# P10_Expander.net
KiCad netlist of a schematic drawn in Altium Designer
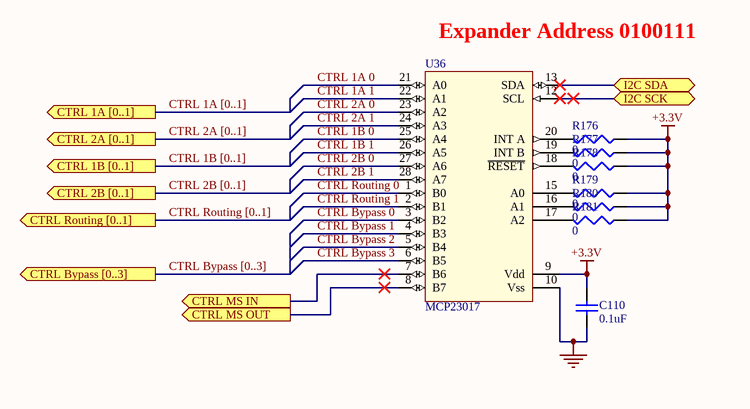
[diagram p0: P10_Expander.SchDoc]

(export (version "E")
  (design (tool "Eeschema 10.0.6"))
  (components
    (comp (ref "C110")
      (value "0.1uF")
      (footprint "CAP 0603 (1608 metric)")
      (description "Capacitor (Semiconductor SIM Model)")
      (libsource (lib "Miscellaneous Devices") (part "Cap Semi"))
    )
    (comp (ref "R176")
      (value "0")
      (footprint "RES 0603 (1608 metric)")
      (description "Resistor")
      (libsource (lib "Miscellaneous Devices") (part "Res3"))
    )
    (comp (ref "R177")
      (value "0")
      (footprint "RES 0603 (1608 metric)")
      (description "Resistor")
      (libsource (lib "Miscellaneous Devices") (part "Res3"))
    )
    (comp (ref "R178")
      (value "0")
      (footprint "RES 0603 (1608 metric)")
      (description "Resistor")
      (libsource (lib "Miscellaneous Devices") (part "Res3"))
    )
    (comp (ref "R179")
      (value "0")
      (footprint "RES 0603 (1608 metric)")
      (description "Resistor")
      (libsource (lib "Miscellaneous Devices") (part "Res3"))
    )
    (comp (ref "R180")
      (value "0")
      (footprint "RES 0603 (1608 metric)")
      (description "Resistor")
      (libsource (lib "Miscellaneous Devices") (part "Res3"))
    )
    (comp (ref "R181")
      (value "0")
      (footprint "RES 0603 (1608 metric)")
      (description "Resistor")
      (libsource (lib "Miscellaneous Devices") (part "Res3"))
    )
    (comp (ref "U36")
      (value "MCP23017")
      (description "16b I/O Expander")
      (libsource (lib "FilterPoC") (part "MCP23017"))
    )
  )
  (nets
    (net (code "1") (name "+3.3V") (class "Default")
      (node (ref "C110") (pin "1") (pinfunction "1_1") (pintype "passive"))
      (node (ref "R176") (pin "1") (pinfunction "1_1") (pintype "passive"))
      (node (ref "R177") (pin "1") (pinfunction "1_1") (pintype "passive"))
      (node (ref "R178") (pin "1") (pinfunction "1_1") (pintype "passive"))
      (node (ref "R179") (pin "1") (pinfunction "1_1") (pintype "passive"))
      (node (ref "R180") (pin "1") (pinfunction "1_1") (pintype "passive"))
      (node (ref "R181") (pin "1") (pinfunction "1_1") (pintype "passive"))
      (node (ref "U36") (pin "9") (pinfunction "Vdd_9") (pintype "power_in"))
    )
    (net (code "2") (name "/CTRL 1A 0") (class "Default")
      (node (ref "U36") (pin "21") (pinfunction "A0_21") (pintype "bidirectional"))
    )
    (net (code "3") (name "/CTRL 1A 1") (class "Default")
      (node (ref "U36") (pin "22") (pinfunction "A1_22") (pintype "bidirectional"))
    )
    (net (code "4") (name "/CTRL 1B 0") (class "Default")
      (node (ref "U36") (pin "25") (pinfunction "A4_25") (pintype "bidirectional"))
    )
    (net (code "5") (name "/CTRL 1B 1") (class "Default")
      (node (ref "U36") (pin "26") (pinfunction "A5_26") (pintype "bidirectional"))
    )
    (net (code "6") (name "/CTRL 2A 0") (class "Default")
      (node (ref "U36") (pin "23") (pinfunction "A2_23") (pintype "bidirectional"))
    )
    (net (code "7") (name "/CTRL 2A 1") (class "Default")
      (node (ref "U36") (pin "24") (pinfunction "A3_24") (pintype "bidirectional"))
    )
    (net (code "8") (name "/CTRL 2B 0") (class "Default")
      (node (ref "U36") (pin "27") (pinfunction "A6_27") (pintype "bidirectional"))
    )
    (net (code "9") (name "/CTRL 2B 1") (class "Default")
      (node (ref "U36") (pin "28") (pinfunction "A7_28") (pintype "bidirectional"))
    )
    (net (code "10") (name "/CTRL Bypass 0") (class "Default")
      (node (ref "U36") (pin "3") (pinfunction "B2_3") (pintype "bidirectional"))
    )
    (net (code "11") (name "/CTRL Bypass 1") (class "Default")
      (node (ref "U36") (pin "4") (pinfunction "B3_4") (pintype "bidirectional"))
    )
    (net (code "12") (name "/CTRL Bypass 2") (class "Default")
      (node (ref "U36") (pin "5") (pinfunction "B4_5") (pintype "bidirectional"))
    )
    (net (code "13") (name "/CTRL Bypass 3") (class "Default")
      (node (ref "U36") (pin "6") (pinfunction "B5_6") (pintype "bidirectional"))
    )
    (net (code "14") (name "/CTRL MS IN") (class "Default")
      (node (ref "U36") (pin "7") (pinfunction "B6_7") (pintype "bidirectional"))
    )
    (net (code "15") (name "/CTRL MS OUT") (class "Default")
      (node (ref "U36") (pin "8") (pinfunction "B7_8") (pintype "bidirectional"))
    )
    (net (code "16") (name "/CTRL Routing 0") (class "Default")
      (node (ref "U36") (pin "1") (pinfunction "B0_1") (pintype "bidirectional"))
    )
    (net (code "17") (name "/CTRL Routing 1") (class "Default")
      (node (ref "U36") (pin "2") (pinfunction "B1_2") (pintype "bidirectional"))
    )
    (net (code "18") (name "/I2C SCK") (class "Default")
      (node (ref "U36") (pin "12") (pinfunction "SCL_12") (pintype "input+no_connect"))
    )
    (net (code "19") (name "/I2C SDA") (class "Default")
      (node (ref "U36") (pin "13") (pinfunction "SDA_13") (pintype "bidirectional+no_connect"))
    )
    (net (code "26") (name "GND") (class "Default")
      (node (ref "C110") (pin "2") (pinfunction "2_2") (pintype "passive"))
      (node (ref "U36") (pin "10") (pinfunction "Vss_10") (pintype "power_in"))
    )
    (net (code "27") (name "Net-(R179-Pad2)") (class "Default")
      (node (ref "R179") (pin "2") (pinfunction "2_2") (pintype "passive"))
      (node (ref "U36") (pin "15") (pinfunction "A0_15") (pintype "passive"))
    )
    (net (code "28") (name "Net-(R180-Pad2)") (class "Default")
      (node (ref "R180") (pin "2") (pinfunction "2_2") (pintype "passive"))
      (node (ref "U36") (pin "16") (pinfunction "A1_16") (pintype "passive"))
    )
    (net (code "29") (name "Net-(R181-Pad2)") (class "Default")
      (node (ref "R181") (pin "2") (pinfunction "2_2") (pintype "passive"))
      (node (ref "U36") (pin "17") (pinfunction "A2_17") (pintype "passive"))
    )
    (net (code "30") (name "Net-(U36-INT_A)") (class "Default")
      (node (ref "R176") (pin "2") (pinfunction "2_2") (pintype "passive"))
      (node (ref "U36") (pin "20") (pinfunction "INT_A_20") (pintype "output"))
    )
    (net (code "31") (name "Net-(U36-INT_B)") (class "Default")
      (node (ref "R177") (pin "2") (pinfunction "2_2") (pintype "passive"))
      (node (ref "U36") (pin "19") (pinfunction "INT_B_19") (pintype "output"))
    )
    (net (code "32") (name "Net-(U36-~{RESET})") (class "Default")
      (node (ref "R178") (pin "2") (pinfunction "2_2") (pintype "passive"))
      (node (ref "U36") (pin "18") (pinfunction "~{RESET}_18") (pintype "output"))
    )
  )
)
